# TEST_CPU.net
KiCad netlist of a schematic drawn in EAGLE
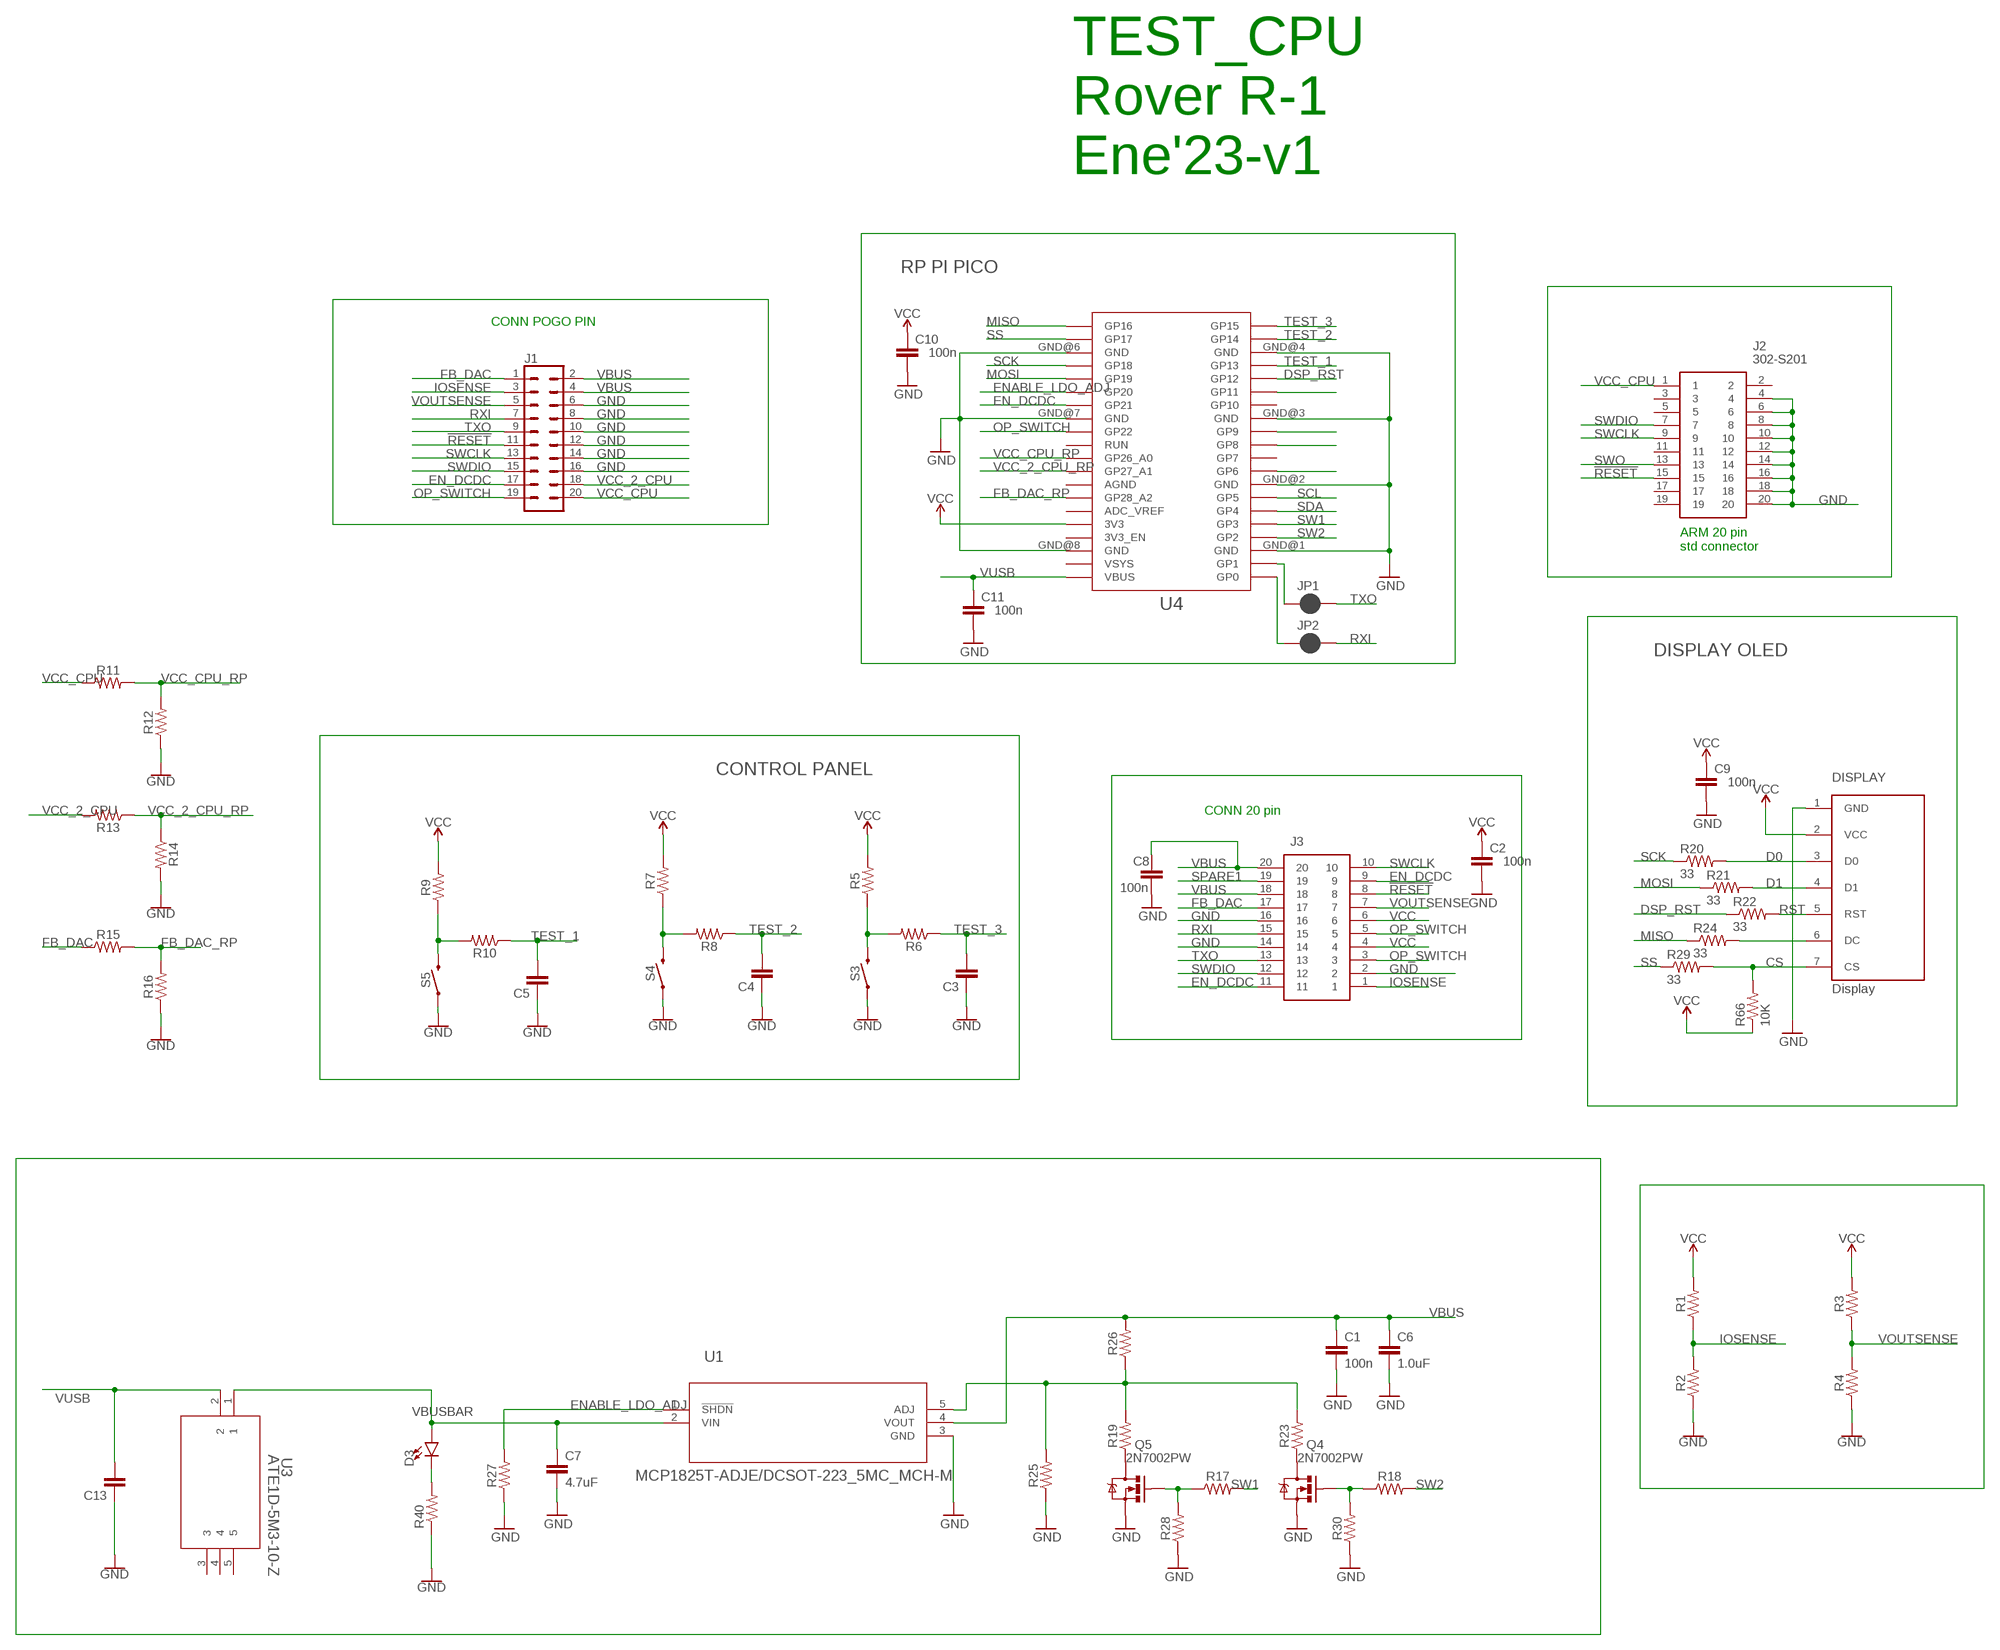
[diagram p0: schematic, sheet 1]

(export (version "E")
  (design (tool "Eeschema 10.0.6"))
  (components
    (comp (ref "C1")
      (value "100n")
      (footprint "eagle-import:0805")
      (libsource (lib "eagle-import") (part "1.0UF-0805-25V-(+80/-20%)"))
    )
    (comp (ref "C2")
      (value "100n")
      (footprint "eagle-import:0805")
      (libsource (lib "eagle-import") (part "1.0UF-0805-25V-(+80/-20%)"))
    )
    (comp (ref "C3")
      (value "C-EUC0805")
      (footprint "eagle-import:C0805")
      (libsource (lib "eagle-import") (part "C-EUC0805"))
    )
    (comp (ref "C4")
      (value "C-EUC0805")
      (footprint "eagle-import:C0805")
      (libsource (lib "eagle-import") (part "C-EUC0805"))
    )
    (comp (ref "C5")
      (value "C-EUC0805")
      (footprint "eagle-import:C0805")
      (libsource (lib "eagle-import") (part "C-EUC0805"))
    )
    (comp (ref "C6")
      (value "1.0uF")
      (footprint "eagle-import:0805")
      (libsource (lib "eagle-import") (part "1.0UF-0805-25V-(+80/-20%)"))
    )
    (comp (ref "C7")
      (value "4.7uF")
      (footprint "eagle-import:0603")
      (libsource (lib "eagle-import") (part "4.7UF0603"))
    )
    (comp (ref "C8")
      (value "100n")
      (footprint "eagle-import:0805")
      (libsource (lib "eagle-import") (part "1.0UF-0805-25V-(+80/-20%)"))
    )
    (comp (ref "C9")
      (value "100n")
      (footprint "eagle-import:0805")
      (libsource (lib "eagle-import") (part "1.0UF-0805-25V-(+80/-20%)"))
    )
    (comp (ref "C10")
      (value "100n")
      (footprint "eagle-import:0805")
      (libsource (lib "eagle-import") (part "1.0UF-0805-25V-(+80/-20%)"))
    )
    (comp (ref "C11")
      (value "100n")
      (footprint "eagle-import:0805")
      (libsource (lib "eagle-import") (part "1.0UF-0805-25V-(+80/-20%)"))
    )
    (comp (ref "C13")
      (value "C-EUC0805")
      (footprint "eagle-import:C0805")
      (libsource (lib "eagle-import") (part "C-EUC0805"))
    )
    (comp (ref "D3")
      (value "LED3MM")
      (footprint "eagle-import:LED_3MM")
      (libsource (lib "eagle-import") (part "LED3MM"))
    )
    (comp (ref "DISPLAY")
      (value "Display")
      (footprint "eagle-import:OLED_LCD")
      (libsource (lib "eagle-import") (part "OLED_LCD"))
    )
    (comp (ref "J1")
      (value "CONN_10X2")
      (footprint "eagle-import:2X10")
      (libsource (lib "eagle-import") (part "CONN_10X2"))
    )
    (comp (ref "J2")
      (value "302-S201")
      (footprint "eagle-import:SHDR20W66P254_2X10_3300X905X90")
      (libsource (lib "eagle-import") (part "302-S201"))
    )
    (comp (ref "J3")
      (value "DF40C-20DP-0.4V_51_")
      (footprint "eagle-import:DF40C-20DPA")
      (fields
        (field (name "ARROW_PART_NUMBER") "DF40C-20DP-0.4V(51)")
        (field (name "MOUSER_PART_NUMBER") "798-DF40C20DP0.4V51")
      )
      (libsource (lib "eagle-import") (part "DF40C-20DP-0.4V_51_"))
    )
    (comp (ref "JP1")
      (value "JUMPER-SMT_2_NC_PASTE_SILK")
      (footprint "eagle-import:SMT-JUMPER_2_NC_PASTE_SILK")
      (libsource (lib "eagle-import") (part "JUMPER-SMT_2_NC_PASTE_SILK"))
    )
    (comp (ref "JP2")
      (value "JUMPER-SMT_2_NC_PASTE_SILK")
      (footprint "eagle-import:SMT-JUMPER_2_NC_PASTE_SILK")
      (libsource (lib "eagle-import") (part "JUMPER-SMT_2_NC_PASTE_SILK"))
    )
    (comp (ref "Q4")
      (value "2N7002PW")
      (footprint "eagle-import:SOT323")
      (libsource (lib "eagle-import") (part "MOSFET-NCHANNEL2N7002PW"))
    )
    (comp (ref "Q5")
      (value "2N7002PW")
      (footprint "eagle-import:SOT323")
      (libsource (lib "eagle-import") (part "MOSFET-NCHANNEL2N7002PW"))
    )
    (comp (ref "R1")
      (value "RESISTOR0805")
      (footprint "eagle-import:0805")
      (libsource (lib "eagle-import") (part "RESISTOR0805"))
    )
    (comp (ref "R2")
      (value "RESISTOR0805")
      (footprint "eagle-import:0805")
      (libsource (lib "eagle-import") (part "RESISTOR0805"))
    )
    (comp (ref "R3")
      (value "RESISTOR0805")
      (footprint "eagle-import:0805")
      (libsource (lib "eagle-import") (part "RESISTOR0805"))
    )
    (comp (ref "R4")
      (value "RESISTOR0805")
      (footprint "eagle-import:0805")
      (libsource (lib "eagle-import") (part "RESISTOR0805"))
    )
    (comp (ref "R5")
      (value "RESISTOR0805")
      (footprint "eagle-import:0805")
      (libsource (lib "eagle-import") (part "RESISTOR0805"))
    )
    (comp (ref "R6")
      (value "RESISTOR0805")
      (footprint "eagle-import:0805")
      (libsource (lib "eagle-import") (part "RESISTOR0805"))
    )
    (comp (ref "R7")
      (value "RESISTOR0805")
      (footprint "eagle-import:0805")
      (libsource (lib "eagle-import") (part "RESISTOR0805"))
    )
    (comp (ref "R8")
      (value "RESISTOR0805")
      (footprint "eagle-import:0805")
      (libsource (lib "eagle-import") (part "RESISTOR0805"))
    )
    (comp (ref "R9")
      (value "RESISTOR0805")
      (footprint "eagle-import:0805")
      (libsource (lib "eagle-import") (part "RESISTOR0805"))
    )
    (comp (ref "R10")
      (value "RESISTOR0805")
      (footprint "eagle-import:0805")
      (libsource (lib "eagle-import") (part "RESISTOR0805"))
    )
    (comp (ref "R11")
      (value "RESISTOR0805")
      (footprint "eagle-import:0805")
      (libsource (lib "eagle-import") (part "RESISTOR0805"))
    )
    (comp (ref "R12")
      (value "RESISTOR0805")
      (footprint "eagle-import:0805")
      (libsource (lib "eagle-import") (part "RESISTOR0805"))
    )
    (comp (ref "R13")
      (value "RESISTOR0805")
      (footprint "eagle-import:0805")
      (libsource (lib "eagle-import") (part "RESISTOR0805"))
    )
    (comp (ref "R14")
      (value "RESISTOR0805")
      (footprint "eagle-import:0805")
      (libsource (lib "eagle-import") (part "RESISTOR0805"))
    )
    (comp (ref "R15")
      (value "RESISTOR0805")
      (footprint "eagle-import:0805")
      (libsource (lib "eagle-import") (part "RESISTOR0805"))
    )
    (comp (ref "R16")
      (value "RESISTOR0805")
      (footprint "eagle-import:0805")
      (libsource (lib "eagle-import") (part "RESISTOR0805"))
    )
    (comp (ref "R17")
      (value "RESISTOR0805")
      (footprint "eagle-import:0805")
      (libsource (lib "eagle-import") (part "RESISTOR0805"))
    )
    (comp (ref "R18")
      (value "RESISTOR0805")
      (footprint "eagle-import:0805")
      (libsource (lib "eagle-import") (part "RESISTOR0805"))
    )
    (comp (ref "R19")
      (value "RESISTOR0805")
      (footprint "eagle-import:0805")
      (libsource (lib "eagle-import") (part "RESISTOR0805"))
    )
    (comp (ref "R20")
      (value "33")
      (footprint "eagle-import:0805")
      (libsource (lib "eagle-import") (part "RESISTOR0805-RES"))
    )
    (comp (ref "R21")
      (value "33")
      (footprint "eagle-import:0805")
      (libsource (lib "eagle-import") (part "RESISTOR0805-RES"))
    )
    (comp (ref "R22")
      (value "33")
      (footprint "eagle-import:0805")
      (libsource (lib "eagle-import") (part "RESISTOR0805-RES"))
    )
    (comp (ref "R23")
      (value "RESISTOR0805")
      (footprint "eagle-import:0805")
      (libsource (lib "eagle-import") (part "RESISTOR0805"))
    )
    (comp (ref "R24")
      (value "33")
      (footprint "eagle-import:0805")
      (libsource (lib "eagle-import") (part "RESISTOR0805-RES"))
    )
    (comp (ref "R25")
      (value "RESISTOR0805")
      (footprint "eagle-import:0805")
      (libsource (lib "eagle-import") (part "RESISTOR0805"))
    )
    (comp (ref "R26")
      (value "RESISTOR0805")
      (footprint "eagle-import:0805")
      (libsource (lib "eagle-import") (part "RESISTOR0805"))
    )
    (comp (ref "R27")
      (value "RESISTOR0805")
      (footprint "eagle-import:0805")
      (libsource (lib "eagle-import") (part "RESISTOR0805"))
    )
    (comp (ref "R28")
      (value "RESISTOR0805")
      (footprint "eagle-import:0805")
      (libsource (lib "eagle-import") (part "RESISTOR0805"))
    )
    (comp (ref "R29")
      (value "33")
      (footprint "eagle-import:0805")
      (libsource (lib "eagle-import") (part "RESISTOR0805-RES"))
    )
    (comp (ref "R30")
      (value "RESISTOR0805")
      (footprint "eagle-import:0805")
      (libsource (lib "eagle-import") (part "RESISTOR0805"))
    )
    (comp (ref "R40")
      (value "10K")
      (footprint "eagle-import:0805")
      (libsource (lib "eagle-import") (part "RESISTOR0805-RES"))
    )
    (comp (ref "R66")
      (value "10K")
      (footprint "eagle-import:0805")
      (libsource (lib "eagle-import") (part "RESISTOR0805-RES"))
    )
    (comp (ref "S3")
      (value "MOMENTARY-SWITCH-SPST-SMD-5.2MM")
      (footprint "eagle-import:TACTILE_SWITCH_SMD_5.2MM")
      (libsource (lib "eagle-import") (part "MOMENTARY-SWITCH-SPST-SMD-5.2MM"))
    )
    (comp (ref "S4")
      (value "MOMENTARY-SWITCH-SPST-SMD-5.2MM")
      (footprint "eagle-import:TACTILE_SWITCH_SMD_5.2MM")
      (libsource (lib "eagle-import") (part "MOMENTARY-SWITCH-SPST-SMD-5.2MM"))
    )
    (comp (ref "S5")
      (value "MOMENTARY-SWITCH-SPST-SMD-5.2MM")
      (footprint "eagle-import:TACTILE_SWITCH_SMD_5.2MM")
      (libsource (lib "eagle-import") (part "MOMENTARY-SWITCH-SPST-SMD-5.2MM"))
    )
    (comp (ref "U1")
      (value "MCP1825T-ADJE/DCSOT-223_5MC_MCH-M")
      (footprint "eagle-import:SOT-223_5MC_MCH-M")
      (fields (field (name "MANUFACTURER_PART_NUMBER") "MCP1825T-ADJE/DC"))
      (libsource (lib "eagle-import") (part "MCP1825T-ADJE/DCSOT-223_5MC_MCH-M"))
    )
    (comp (ref "U3")
      (value "ATE1D-5M3-10-Z")
      (footprint "eagle-import:SPDT05_ATE1D_9P5X8_NDC")
      (fields (field (name "COPYRIGHT") "Copyright (C) 2022 Ultra Librarian. All rights reserved."))
      (libsource (lib "eagle-import") (part "ATE1D-5M3-10-Z"))
    )
    (comp (ref "U4")
      (value "RPI_PICO_IG-TH")
      (footprint "eagle-import:RPI_PICO_TH")
      (libsource (lib "eagle-import") (part "RPI_PICO_IG-TH"))
    )
  )
  (nets
    (net (code "1") (name "/CS") (class "Default")
      (node (ref "DISPLAY") (pin "7") (pinfunction "CS_7") (pintype "bidirectional"))
      (node (ref "R29") (pin "2") (pinfunction "2_2") (pintype "passive"))
      (node (ref "R66") (pin "2") (pinfunction "2_2") (pintype "passive"))
    )
    (net (code "2") (name "/D0") (class "Default")
      (node (ref "DISPLAY") (pin "3") (pinfunction "D0_3") (pintype "bidirectional"))
      (node (ref "R20") (pin "2") (pinfunction "2_2") (pintype "passive"))
    )
    (net (code "3") (name "/D1") (class "Default")
      (node (ref "DISPLAY") (pin "4") (pinfunction "D1_4") (pintype "bidirectional"))
      (node (ref "R21") (pin "2") (pinfunction "2_2") (pintype "passive"))
    )
    (net (code "4") (name "/DSP_RST") (class "Default")
      (node (ref "R22") (pin "1") (pinfunction "1_1") (pintype "passive"))
      (node (ref "U4") (pin "GP12") (pinfunction "GP12_GP12") (pintype "bidirectional"))
    )
    (net (code "5") (name "/ENABLE_LDO_ADJ") (class "Default")
      (node (ref "R27") (pin "2") (pinfunction "2_2") (pintype "passive"))
      (node (ref "U1") (pin "1") (pinfunction "~{SHDN}_1") (pintype "passive"))
      (node (ref "U4") (pin "GP20") (pinfunction "GP20_GP20") (pintype "bidirectional"))
    )
    (net (code "6") (name "/EN_DCDC") (class "Default")
      (node (ref "J1") (pin "17") (pinfunction "17_17") (pintype "passive"))
      (node (ref "J3") (pin "11") (pinfunction "11_11") (pintype "bidirectional"))
      (node (ref "J3") (pin "9") (pinfunction "9_9") (pintype "bidirectional"))
      (node (ref "U4") (pin "GP21") (pinfunction "GP21_GP21") (pintype "bidirectional"))
    )
    (net (code "7") (name "/FB_DAC") (class "Default")
      (node (ref "J1") (pin "1") (pinfunction "1_1") (pintype "passive"))
      (node (ref "J3") (pin "17") (pinfunction "17_17") (pintype "bidirectional"))
      (node (ref "R15") (pin "1") (pinfunction "1_1") (pintype "passive"))
    )
    (net (code "8") (name "/FB_DAC_RP") (class "Default")
      (node (ref "R15") (pin "2") (pinfunction "2_2") (pintype "passive"))
      (node (ref "R16") (pin "2") (pinfunction "2_2") (pintype "passive"))
      (node (ref "U4") (pin "GP28_A2") (pinfunction "GP28_A2_GP28_A2") (pintype "bidirectional"))
    )
    (net (code "9") (name "/IOSENSE") (class "Default")
      (node (ref "J1") (pin "3") (pinfunction "3_3") (pintype "passive"))
      (node (ref "J3") (pin "1") (pinfunction "1_1") (pintype "bidirectional"))
      (node (ref "R1") (pin "1") (pinfunction "1_1") (pintype "passive"))
      (node (ref "R2") (pin "2") (pinfunction "2_2") (pintype "passive"))
    )
    (net (code "10") (name "/MISO") (class "Default")
      (node (ref "R24") (pin "1") (pinfunction "1_1") (pintype "passive"))
      (node (ref "U4") (pin "GP16") (pinfunction "GP16_GP16") (pintype "bidirectional"))
    )
    (net (code "11") (name "/MOSI") (class "Default")
      (node (ref "R21") (pin "1") (pinfunction "1_1") (pintype "passive"))
      (node (ref "U4") (pin "GP19") (pinfunction "GP19_GP19") (pintype "bidirectional"))
    )
    (net (code "12") (name "/OP_SWITCH") (class "Default")
      (node (ref "J1") (pin "19") (pinfunction "19_19") (pintype "passive"))
      (node (ref "J3") (pin "3") (pinfunction "3_3") (pintype "bidirectional"))
      (node (ref "J3") (pin "5") (pinfunction "5_5") (pintype "bidirectional"))
      (node (ref "U4") (pin "GP22") (pinfunction "GP22_GP22") (pintype "bidirectional"))
    )
    (net (code "13") (name "/RST") (class "Default")
      (node (ref "DISPLAY") (pin "5") (pinfunction "RST_5") (pintype "bidirectional"))
      (node (ref "R22") (pin "2") (pinfunction "2_2") (pintype "passive"))
    )
    (net (code "14") (name "/RXI") (class "Default")
      (node (ref "J1") (pin "7") (pinfunction "7_7") (pintype "passive"))
      (node (ref "J3") (pin "15") (pinfunction "15_15") (pintype "bidirectional"))
      (node (ref "JP2") (pin "2") (pinfunction "2_2") (pintype "passive"))
    )
    (net (code "15") (name "/SCK") (class "Default")
      (node (ref "R20") (pin "1") (pinfunction "1_1") (pintype "passive"))
      (node (ref "U4") (pin "GP18") (pinfunction "GP18_GP18") (pintype "bidirectional"))
    )
    (net (code "16") (name "/SCL") (class "Default")
      (node (ref "U4") (pin "GP5") (pinfunction "GP5_GP5") (pintype "bidirectional"))
    )
    (net (code "17") (name "/SDA") (class "Default")
      (node (ref "U4") (pin "GP4") (pinfunction "GP4_GP4") (pintype "bidirectional"))
    )
    (net (code "18") (name "/SPARE1") (class "Default")
      (node (ref "J3") (pin "19") (pinfunction "19_19") (pintype "bidirectional"))
    )
    (net (code "19") (name "/SS") (class "Default")
      (node (ref "R29") (pin "1") (pinfunction "1_1") (pintype "passive"))
      (node (ref "U4") (pin "GP17") (pinfunction "GP17_GP17") (pintype "bidirectional"))
    )
    (net (code "20") (name "/SW1") (class "Default")
      (node (ref "R17") (pin "2") (pinfunction "2_2") (pintype "passive"))
      (node (ref "U4") (pin "GP3") (pinfunction "GP3_GP3") (pintype "bidirectional"))
    )
    (net (code "21") (name "/SW2") (class "Default")
      (node (ref "R18") (pin "2") (pinfunction "2_2") (pintype "passive"))
      (node (ref "U4") (pin "GP2") (pinfunction "GP2_GP2") (pintype "bidirectional"))
    )
    (net (code "22") (name "/SWCLK") (class "Default")
      (node (ref "J1") (pin "13") (pinfunction "13_13") (pintype "passive"))
      (node (ref "J2") (pin "9") (pinfunction "9_9") (pintype "bidirectional"))
      (node (ref "J3") (pin "10") (pinfunction "10_10") (pintype "bidirectional"))
    )
    (net (code "23") (name "/SWDIO") (class "Default")
      (node (ref "J1") (pin "15") (pinfunction "15_15") (pintype "passive"))
      (node (ref "J2") (pin "7") (pinfunction "7_7") (pintype "bidirectional"))
      (node (ref "J3") (pin "12") (pinfunction "12_12") (pintype "bidirectional"))
    )
    (net (code "24") (name "/SWO") (class "Default")
      (node (ref "J2") (pin "13") (pinfunction "13_13") (pintype "bidirectional"))
    )
    (net (code "25") (name "/TEST_1") (class "Default")
      (node (ref "C5") (pin "2") (pinfunction "2_2") (pintype "passive"))
      (node (ref "R10") (pin "1") (pinfunction "1_1") (pintype "passive"))
      (node (ref "U4") (pin "GP13") (pinfunction "GP13_GP13") (pintype "bidirectional"))
    )
    (net (code "26") (name "/TEST_2") (class "Default")
      (node (ref "C4") (pin "2") (pinfunction "2_2") (pintype "passive"))
      (node (ref "R8") (pin "1") (pinfunction "1_1") (pintype "passive"))
      (node (ref "U4") (pin "GP14") (pinfunction "GP14_GP14") (pintype "bidirectional"))
    )
    (net (code "27") (name "/TEST_3") (class "Default")
      (node (ref "C3") (pin "2") (pinfunction "2_2") (pintype "passive"))
      (node (ref "R6") (pin "1") (pinfunction "1_1") (pintype "passive"))
      (node (ref "U4") (pin "GP15") (pinfunction "GP15_GP15") (pintype "bidirectional"))
    )
    (net (code "28") (name "/TXO") (class "Default")
      (node (ref "J1") (pin "9") (pinfunction "9_9") (pintype "passive"))
      (node (ref "J3") (pin "13") (pinfunction "13_13") (pintype "bidirectional"))
      (node (ref "JP1") (pin "2") (pinfunction "2_2") (pintype "passive"))
    )
    (net (code "29") (name "/VBUS") (class "Default")
      (node (ref "C1") (pin "1") (pinfunction "1_1") (pintype "passive"))
      (node (ref "C6") (pin "1") (pinfunction "1_1") (pintype "passive"))
      (node (ref "C8") (pin "1") (pinfunction "1_1") (pintype "passive"))
      (node (ref "J1") (pin "2") (pinfunction "2_2") (pintype "passive"))
      (node (ref "J1") (pin "4") (pinfunction "4_4") (pintype "passive"))
      (node (ref "J3") (pin "18") (pinfunction "18_18") (pintype "bidirectional"))
      (node (ref "J3") (pin "20") (pinfunction "20_20") (pintype "bidirectional"))
      (node (ref "R26") (pin "2") (pinfunction "2_2") (pintype "passive"))
      (node (ref "U1") (pin "4") (pinfunction "VOUT_4") (pintype "passive"))
    )
    (net (code "30") (name "/VBUSBAR") (class "Default")
      (node (ref "C7") (pin "1") (pinfunction "1_1") (pintype "passive"))
      (node (ref "D3") (pin "A") (pinfunction "A_A") (pintype "passive"))
      (node (ref "U1") (pin "2") (pinfunction "VIN_2") (pintype "passive"))
      (node (ref "U3") (pin "1") (pinfunction "1_1") (pintype "passive"))
    )
    (net (code "31") (name "/VCC_2_CPU") (class "Default")
      (node (ref "J1") (pin "18") (pinfunction "18_18") (pintype "passive"))
      (node (ref "R13") (pin "2") (pinfunction "2_2") (pintype "passive"))
    )
    (net (code "32") (name "/VCC_2_CPU_RP") (class "Default")
      (node (ref "R13") (pin "1") (pinfunction "1_1") (pintype "passive"))
      (node (ref "R14") (pin "1") (pinfunction "1_1") (pintype "passive"))
      (node (ref "U4") (pin "GP27_A1") (pinfunction "GP27_A1_GP27_A1") (pintype "bidirectional"))
    )
    (net (code "33") (name "/VCC_CPU") (class "Default")
      (node (ref "J1") (pin "20") (pinfunction "20_20") (pintype "passive"))
      (node (ref "J2") (pin "1") (pinfunction "1_1") (pintype "bidirectional"))
      (node (ref "R11") (pin "1") (pinfunction "1_1") (pintype "passive"))
    )
    (net (code "34") (name "/VCC_CPU_RP") (class "Default")
      (node (ref "R11") (pin "2") (pinfunction "2_2") (pintype "passive"))
      (node (ref "R12") (pin "2") (pinfunction "2_2") (pintype "passive"))
      (node (ref "U4") (pin "GP26_A0") (pinfunction "GP26_A0_GP26_A0") (pintype "bidirectional"))
    )
    (net (code "35") (name "/VOUTSENSE") (class "Default")
      (node (ref "J1") (pin "5") (pinfunction "5_5") (pintype "passive"))
      (node (ref "J3") (pin "7") (pinfunction "7_7") (pintype "bidirectional"))
      (node (ref "R3") (pin "1") (pinfunction "1_1") (pintype "passive"))
      (node (ref "R4") (pin "2") (pinfunction "2_2") (pintype "passive"))
    )
    (net (code "36") (name "/VUSB") (class "Default")
      (node (ref "C11") (pin "1") (pinfunction "1_1") (pintype "passive"))
      (node (ref "C13") (pin "2") (pinfunction "2_2") (pintype "passive"))
      (node (ref "U3") (pin "2") (pinfunction "2_2") (pintype "passive"))
      (node (ref "U4") (pin "VBUS") (pinfunction "VBUS_VBUS") (pintype "bidirectional"))
    )
    (net (code "37") (name "/~{RESET}") (class "Default")
      (node (ref "J1") (pin "11") (pinfunction "11_11") (pintype "passive"))
      (node (ref "J2") (pin "15") (pinfunction "15_15") (pintype "bidirectional"))
      (node (ref "J3") (pin "8") (pinfunction "8_8") (pintype "bidirectional"))
    )
    (net (code "38") (name "GND") (class "Default")
      (node (ref "C1") (pin "2") (pinfunction "2_2") (pintype "passive"))
      (node (ref "C10") (pin "2") (pinfunction "2_2") (pintype "passive"))
      (node (ref "C11") (pin "2") (pinfunction "2_2") (pintype "passive"))
      (node (ref "C13") (pin "1") (pinfunction "1_1") (pintype "passive"))
      (node (ref "C2") (pin "2") (pinfunction "2_2") (pintype "passive"))
      (node (ref "C3") (pin "1") (pinfunction "1_1") (pintype "passive"))
      (node (ref "C4") (pin "1") (pinfunction "1_1") (pintype "passive"))
      (node (ref "C5") (pin "1") (pinfunction "1_1") (pintype "passive"))
      (node (ref "C6") (pin "2") (pinfunction "2_2") (pintype "passive"))
      (node (ref "C7") (pin "2") (pinfunction "2_2") (pintype "passive"))
      (node (ref "C8") (pin "2") (pinfunction "2_2") (pintype "passive"))
      (node (ref "C9") (pin "2") (pinfunction "2_2") (pintype "passive"))
      (node (ref "DISPLAY") (pin "1") (pinfunction "GND_1") (pintype "bidirectional"))
      (node (ref "J1") (pin "10") (pinfunction "10_10") (pintype "passive"))
      (node (ref "J1") (pin "12") (pinfunction "12_12") (pintype "passive"))
      (node (ref "J1") (pin "14") (pinfunction "14_14") (pintype "passive"))
      (node (ref "J1") (pin "16") (pinfunction "16_16") (pintype "passive"))
      (node (ref "J1") (pin "6") (pinfunction "6_6") (pintype "passive"))
      (node (ref "J1") (pin "8") (pinfunction "8_8") (pintype "passive"))
      (node (ref "J2") (pin "10") (pinfunction "10_10") (pintype "bidirectional"))
      (node (ref "J2") (pin "12") (pinfunction "12_12") (pintype "bidirectional"))
      (node (ref "J2") (pin "14") (pinfunction "14_14") (pintype "bidirectional"))
      (node (ref "J2") (pin "16") (pinfunction "16_16") (pintype "bidirectional"))
      (node (ref "J2") (pin "18") (pinfunction "18_18") (pintype "bidirectional"))
      (node (ref "J2") (pin "20") (pinfunction "20_20") (pintype "bidirectional"))
      (node (ref "J2") (pin "4") (pinfunction "4_4") (pintype "bidirectional"))
      (node (ref "J2") (pin "6") (pinfunction "6_6") (pintype "bidirectional"))
      (node (ref "J2") (pin "8") (pinfunction "8_8") (pintype "bidirectional"))
      (node (ref "J3") (pin "14") (pinfunction "14_14") (pintype "bidirectional"))
      (node (ref "J3") (pin "16") (pinfunction "16_16") (pintype "bidirectional"))
      (node (ref "J3") (pin "2") (pinfunction "2_2") (pintype "bidirectional"))
      (node (ref "Q4") (pin "2") (pinfunction "S_2") (pintype "passive"))
      (node (ref "Q5") (pin "2") (pinfunction "S_2") (pintype "passive"))
      (node (ref "R12") (pin "1") (pinfunction "1_1") (pintype "passive"))
      (node (ref "R14") (pin "2") (pinfunction "2_2") (pintype "passive"))
      (node (ref "R16") (pin "1") (pinfunction "1_1") (pintype "passive"))
      (node (ref "R2") (pin "1") (pinfunction "1_1") (pintype "passive"))
      (node (ref "R25") (pin "1") (pinfunction "1_1") (pintype "passive"))
      (node (ref "R27") (pin "1") (pinfunction "1_1") (pintype "passive"))
      (node (ref "R28") (pin "1") (pinfunction "1_1") (pintype "passive"))
      (node (ref "R30") (pin "1") (pinfunction "1_1") (pintype "passive"))
      (node (ref "R4") (pin "1") (pinfunction "1_1") (pintype "passive"))
      (node (ref "R40") (pin "1") (pinfunction "1_1") (pintype "passive"))
      (node (ref "S3") (pin "1") (pinfunction "1_1") (pintype "passive"))
      (node (ref "S4") (pin "1") (pinfunction "1_1") (pintype "passive"))
      (node (ref "S5") (pin "1") (pinfunction "1_1") (pintype "passive"))
      (node (ref "U1") (pin "3") (pinfunction "GND_3") (pintype "passive"))
      (node (ref "U4") (pin "GND@1") (pinfunction "GND_GND@1") (pintype "bidirectional"))
      (node (ref "U4") (pin "GND@2") (pinfunction "GND_GND@2") (pintype "bidirectional"))
      (node (ref "U4") (pin "GND@3") (pinfunction "GND_GND@3") (pintype "bidirectional"))
      (node (ref "U4") (pin "GND@4") (pinfunction "GND_GND@4") (pintype "bidirectional"))
      (node (ref "U4") (pin "GND@6") (pinfunction "GND_GND@6") (pintype "bidirectional"))
      (node (ref "U4") (pin "GND@7") (pinfunction "GND_GND@7") (pintype "bidirectional"))
      (node (ref "U4") (pin "GND@8") (pinfunction "GND_GND@8") (pintype "bidirectional"))
    )
    (net (code "39") (name "Net-(D3-C)") (class "Default")
      (node (ref "D3") (pin "K") (pinfunction "C_K") (pintype "passive"))
      (node (ref "R40") (pin "2") (pinfunction "2_2") (pintype "passive"))
    )
    (net (code "40") (name "Net-(DISPLAY-DC)") (class "Default")
      (node (ref "DISPLAY") (pin "6") (pinfunction "DC_6") (pintype "bidirectional"))
      (node (ref "R24") (pin "2") (pinfunction "2_2") (pintype "passive"))
    )
    (net (code "41") (name "Net-(JP1-Pad1)") (class "Default")
      (node (ref "JP1") (pin "1") (pinfunction "1_1") (pintype "passive"))
      (node (ref "U4") (pin "GP1") (pinfunction "GP1_GP1") (pintype "bidirectional"))
    )
    (net (code "42") (name "Net-(JP2-Pad1)") (class "Default")
      (node (ref "JP2") (pin "1") (pinfunction "1_1") (pintype "passive"))
      (node (ref "U4") (pin "GP0") (pinfunction "GP0_GP0") (pintype "bidirectional"))
    )
    (net (code "43") (name "Net-(Q4-D)") (class "Default")
      (node (ref "Q4") (pin "3") (pinfunction "D_3") (pintype "passive"))
      (node (ref "R23") (pin "1") (pinfunction "1_1") (pintype "passive"))
    )
    (net (code "44") (name "Net-(Q4-G)") (class "Default")
      (node (ref "Q4") (pin "1") (pinfunction "G_1") (pintype "passive"))
      (node (ref "R18") (pin "1") (pinfunction "1_1") (pintype "passive"))
      (node (ref "R30") (pin "2") (pinfunction "2_2") (pintype "passive"))
    )
    (net (code "45") (name "Net-(Q5-D)") (class "Default")
      (node (ref "Q5") (pin "3") (pinfunction "D_3") (pintype "passive"))
      (node (ref "R19") (pin "1") (pinfunction "1_1") (pintype "passive"))
    )
    (net (code "46") (name "Net-(Q5-G)") (class "Default")
      (node (ref "Q5") (pin "1") (pinfunction "G_1") (pintype "passive"))
      (node (ref "R17") (pin "1") (pinfunction "1_1") (pintype "passive"))
      (node (ref "R28") (pin "2") (pinfunction "2_2") (pintype "passive"))
    )
    (net (code "47") (name "Net-(S3-2)") (class "Default")
      (node (ref "R5") (pin "1") (pinfunction "1_1") (pintype "passive"))
      (node (ref "R6") (pin "2") (pinfunction "2_2") (pintype "passive"))
      (node (ref "S3") (pin "3") (pinfunction "2_3") (pintype "passive"))
    )
    (net (code "48") (name "Net-(S4-2)") (class "Default")
      (node (ref "R7") (pin "1") (pinfunction "1_1") (pintype "passive"))
      (node (ref "R8") (pin "2") (pinfunction "2_2") (pintype "passive"))
      (node (ref "S4") (pin "3") (pinfunction "2_3") (pintype "passive"))
    )
    (net (code "49") (name "Net-(S5-2)") (class "Default")
      (node (ref "R10") (pin "2") (pinfunction "2_2") (pintype "passive"))
      (node (ref "R9") (pin "1") (pinfunction "1_1") (pintype "passive"))
      (node (ref "S5") (pin "3") (pinfunction "2_3") (pintype "passive"))
    )
    (net (code "50") (name "Net-(U1-ADJ)") (class "Default")
      (node (ref "R19") (pin "2") (pinfunction "2_2") (pintype "passive"))
      (node (ref "R23") (pin "2") (pinfunction "2_2") (pintype "passive"))
      (node (ref "R25") (pin "2") (pinfunction "2_2") (pintype "passive"))
      (node (ref "R26") (pin "1") (pinfunction "1_1") (pintype "passive"))
      (node (ref "U1") (pin "5") (pinfunction "ADJ_5") (pintype "passive"))
    )
    (net (code "51") (name "VCC") (class "Default")
      (node (ref "C10") (pin "1") (pinfunction "1_1") (pintype "passive"))
      (node (ref "C2") (pin "1") (pinfunction "1_1") (pintype "passive"))
      (node (ref "C9") (pin "1") (pinfunction "1_1") (pintype "passive"))
      (node (ref "DISPLAY") (pin "2") (pinfunction "VCC_2") (pintype "bidirectional"))
      (node (ref "J3") (pin "4") (pinfunction "4_4") (pintype "bidirectional"))
      (node (ref "J3") (pin "6") (pinfunction "6_6") (pintype "bidirectional"))
      (node (ref "R1") (pin "2") (pinfunction "2_2") (pintype "passive"))
      (node (ref "R3") (pin "2") (pinfunction "2_2") (pintype "passive"))
      (node (ref "R5") (pin "2") (pinfunction "2_2") (pintype "passive"))
      (node (ref "R66") (pin "1") (pinfunction "1_1") (pintype "passive"))
      (node (ref "R7") (pin "2") (pinfunction "2_2") (pintype "passive"))
      (node (ref "R9") (pin "2") (pinfunction "2_2") (pintype "passive"))
      (node (ref "U4") (pin "3V3") (pinfunction "3V3_3V3") (pintype "bidirectional"))
    )
    (net (code "52") (name "unconnected-(J2-Pad2)") (class "Default")
      (node (ref "J2") (pin "2") (pinfunction "2_2") (pintype "bidirectional"))
    )
    (net (code "53") (name "unconnected-(J2-Pad3)") (class "Default")
      (node (ref "J2") (pin "3") (pinfunction "3_3") (pintype "bidirectional"))
    )
    (net (code "54") (name "unconnected-(J2-Pad5)") (class "Default")
      (node (ref "J2") (pin "5") (pinfunction "5_5") (pintype "bidirectional"))
    )
    (net (code "55") (name "unconnected-(J2-Pad11)") (class "Default")
      (node (ref "J2") (pin "11") (pinfunction "11_11") (pintype "bidirectional"))
    )
    (net (code "56") (name "unconnected-(J2-Pad17)") (class "Default")
      (node (ref "J2") (pin "17") (pinfunction "17_17") (pintype "bidirectional"))
    )
    (net (code "57") (name "unconnected-(J2-Pad19)") (class "Default")
      (node (ref "J2") (pin "19") (pinfunction "19_19") (pintype "bidirectional"))
    )
    (net (code "58") (name "unconnected-(U3-Pad3)") (class "Default")
      (node (ref "U3") (pin "3") (pinfunction "3_3") (pintype "passive"))
    )
    (net (code "59") (name "unconnected-(U3-Pad4)") (class "Default")
      (node (ref "U3") (pin "4") (pinfunction "4_4") (pintype "passive"))
    )
    (net (code "60") (name "unconnected-(U3-Pad5)") (class "Default")
      (node (ref "U3") (pin "5") (pinfunction "5_5") (pintype "passive"))
    )
    (net (code "61") (name "unconnected-(U4-Pad3V3_EN)") (class "Default")
      (node (ref "U4") (pin "3V3_EN") (pinfunction "3V3_EN_3V3_EN") (pintype "bidirectional"))
    )
    (net (code "62") (name "unconnected-(U4-PadADC_VREF)") (class "Default")
      (node (ref "U4") (pin "ADC_VREF") (pinfunction "ADC_VREF_ADC_VREF") (pintype "bidirectional"))
    )
    (net (code "63") (name "unconnected-(U4-PadAGND)") (class "Default")
      (node (ref "U4") (pin "AGND") (pinfunction "AGND_AGND") (pintype "bidirectional"))
    )
    (net (code "64") (name "unconnected-(U4-PadGP6)") (class "Default")
      (node (ref "U4") (pin "GP6") (pinfunction "GP6_GP6") (pintype "bidirectional"))
    )
    (net (code "65") (name "unconnected-(U4-PadGP7)") (class "Default")
      (node (ref "U4") (pin "GP7") (pinfunction "GP7_GP7") (pintype "bidirectional"))
    )
    (net (code "66") (name "unconnected-(U4-PadGP8)") (class "Default")
      (node (ref "U4") (pin "GP8") (pinfunction "GP8_GP8") (pintype "bidirectional"))
    )
    (net (code "67") (name "unconnected-(U4-PadGP9)") (class "Default")
      (node (ref "U4") (pin "GP9") (pinfunction "GP9_GP9") (pintype "bidirectional"))
    )
    (net (code "68") (name "unconnected-(U4-PadGP10)") (class "Default")
      (node (ref "U4") (pin "GP10") (pinfunction "GP10_GP10") (pintype "bidirectional"))
    )
    (net (code "69") (name "unconnected-(U4-PadGP11)") (class "Default")
      (node (ref "U4") (pin "GP11") (pinfunction "GP11_GP11") (pintype "bidirectional"))
    )
    (net (code "70") (name "unconnected-(U4-PadRUN)") (class "Default")
      (node (ref "U4") (pin "RUN") (pinfunction "RUN_RUN") (pintype "bidirectional"))
    )
    (net (code "71") (name "unconnected-(U4-PadVSYS)") (class "Default")
      (node (ref "U4") (pin "VSYS") (pinfunction "VSYS_VSYS") (pintype "bidirectional"))
    )
  )
)
